# GPRS_ModuleV3R.net
KiCad netlist of a schematic drawn in Altium Designer
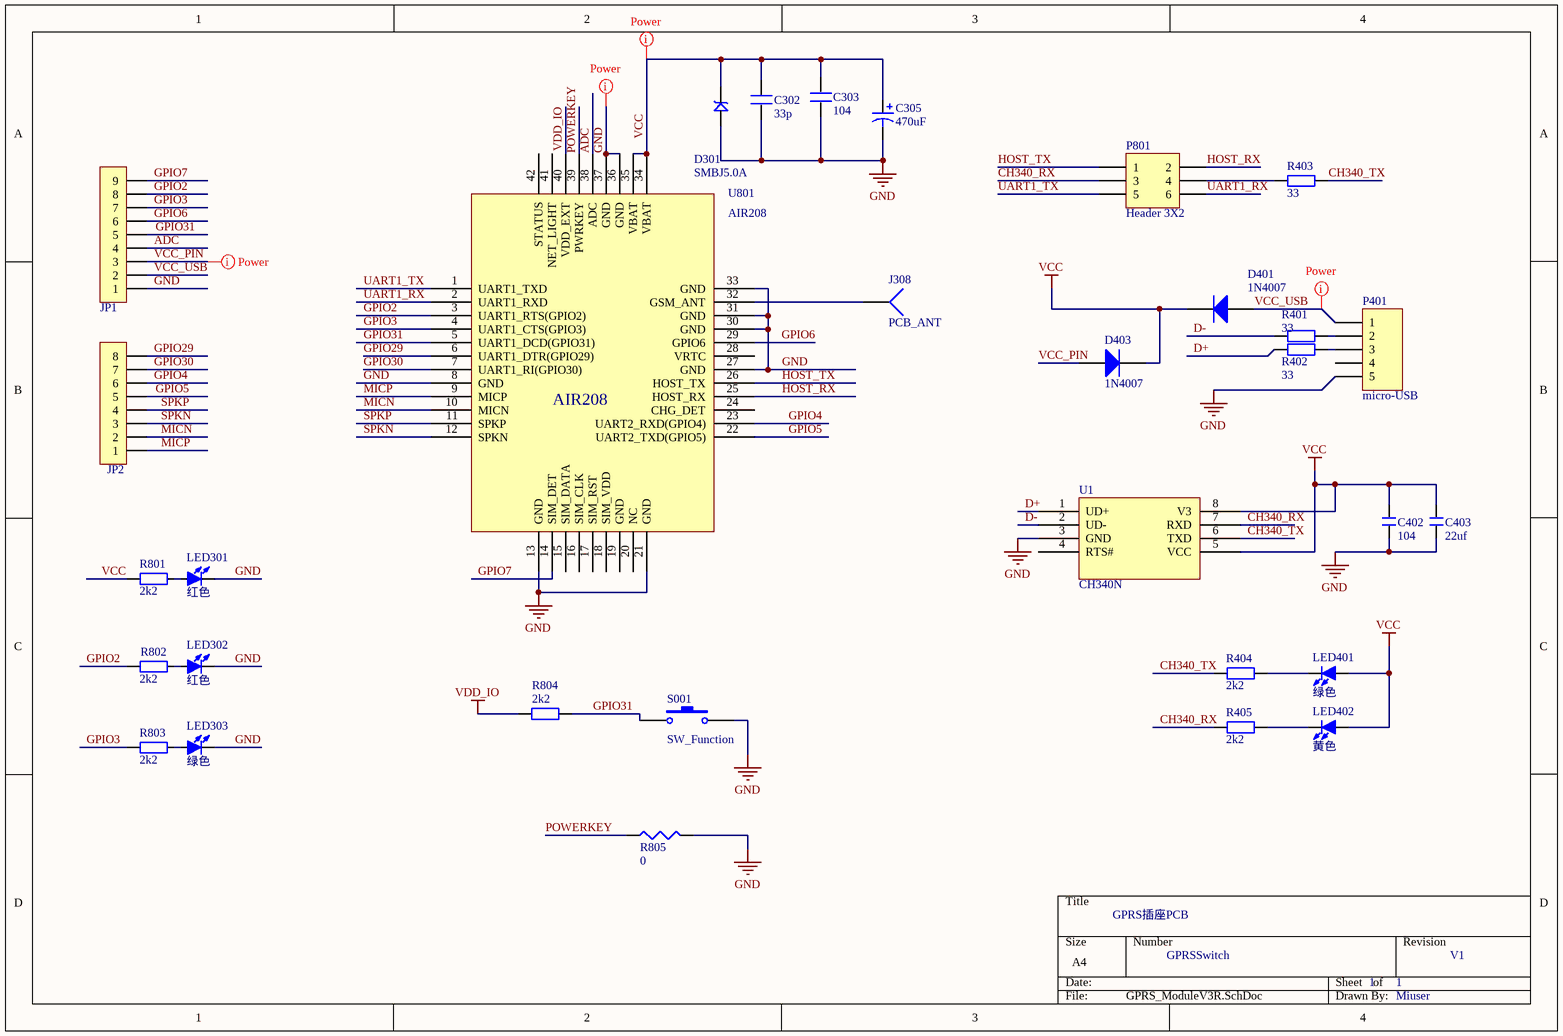
[diagram p0: GPRS_ModuleV3R.SchDoc]

(export (version "E")
  (design (tool "Eeschema 10.0.6"))
  (components
    (comp (ref "C302") (value "33p") (footprint "C 0603") (libsource (lib "PCB_Project") (part "C")))
    (comp (ref "C303") (value "104") (footprint "C 0805") (libsource (lib "PCB_Project") (part "C")))
    (comp (ref "C305")
      (value "470uF")
      (footprint "CD D(7343)")
      (description "Polarized Capacitor (Radial)")
      (fields (field (name "PUBLISHER") "Altium Limited"))
      (libsource (lib "Miscellaneous Devices") (part "Cap Pol1"))
    )
    (comp (ref "C402")
      (value "104")
      (footprint "C 0805")
      (description "无极性贴片电容")
      (fields (field (name "版权归属") "源创客"))
      (libsource (lib "电阻-电容-电感") (part "C"))
    )
    (comp (ref "C403")
      (value "22uf")
      (footprint "C 0805")
      (description "无极性贴片电容")
      (fields (field (name "版权归属") "源创客"))
      (libsource (lib "电阻-电容-电感") (part "C"))
    )
    (comp (ref "D301")
      (value "SMBJ5.0A")
      (footprint "SMC")
      (description "TVS")
      (fields (field (name "ALTIUM_UNNAMED_1") "SMBJ5.0A"))
      (libsource (lib "SIM800C 原理图库") (part "SMBJ"))
    )
    (comp (ref "D401")
      (value "1N4007")
      (footprint "SMB")
      (description "1 Amp General Purpose Rectifier")
      (fields (field (name "PUBLISHER") "Altium Limited"))
      (libsource (lib "Miscellaneous Devices") (part "Diode 1N4001"))
    )
    (comp (ref "D403")
      (value "1N4007")
      (footprint "SMB")
      (description "1 Amp General Purpose Rectifier")
      (fields (field (name "PUBLISHER") "Altium Limited"))
      (libsource (lib "Miscellaneous Devices") (part "Diode 1N4001"))
    )
    (comp (ref "J308")
      (value "PCB_ANT")
      (footprint "GSMANT2")
      (description "Socket")
      (fields (field (name "PUBLISHER") "Altium Limited"))
      (libsource (lib "PCB_Project") (part "Socket"))
    )
    (comp (ref "JP1")
      (value "HDR-1X9")
      (footprint "HDR-1X9")
      (description "9P接插件")
      (fields (field (name "版权归属") "源创客"))
      (libsource (lib "接插件") (part "Header 9"))
    )
    (comp (ref "JP2")
      (value "HDR-1X8")
      (footprint "HDR-1X8")
      (description "8P接插件")
      (fields (field (name "版权归属") "源创客"))
      (libsource (lib "接插件") (part "Header 8"))
    )
    (comp (ref "LED301")
      (value "红色")
      (footprint "LED 0603R")
      (description "贴片LED")
      (fields (field (name "版权归属") "源创客"))
      (libsource (lib "LED") (part "LED-SMD"))
    )
    (comp (ref "LED302")
      (value "红色")
      (footprint "LED 0603R")
      (description "贴片LED")
      (fields (field (name "版权归属") "源创客"))
      (libsource (lib "LED") (part "LED-SMD"))
    )
    (comp (ref "LED303")
      (value "绿色")
      (footprint "LED 0603G")
      (description "贴片LED")
      (fields (field (name "版权归属") "源创客"))
      (libsource (lib "LED") (part "LED-SMD"))
    )
    (comp (ref "LED401")
      (value "绿色")
      (footprint "LED 0603G")
      (description "贴片LED")
      (fields (field (name "版权归属") "源创客"))
      (libsource (lib "LED") (part "LED-SMD"))
    )
    (comp (ref "LED402")
      (value "黄色")
      (footprint "LED 0603Y")
      (description "贴片LED")
      (fields (field (name "版权归属") "源创客"))
      (libsource (lib "LED") (part "LED-SMD"))
    )
    (comp (ref "P401")
      (value "micro-USB")
      (footprint "通讯接口:USB-micro_B")
      (description "Header, 5-Pin")
      (fields (field (name "PUBLISHER") "Altium Limited"))
      (libsource (lib "Miscellaneous Connectors") (part "Header 5"))
    )
    (comp (ref "P801")
      (value "Header 3X2")
      (footprint "HDR2X3")
      (description "Header, 3-Pin, Dual row")
      (fields (field (name "PUBLISHER") "Altium Limited"))
      (libsource (lib "Miscellaneous Connectors") (part "Header 3X2"))
    )
    (comp (ref "R401")
      (value "33")
      (footprint "R 0603")
      (description "Resistor")
      (fields (field (name "PUBLISHER") "Altium Limited"))
      (libsource (lib "Miscellaneous Devices") (part "Res2"))
    )
    (comp (ref "R402")
      (value "33")
      (footprint "R 0603")
      (description "Resistor")
      (fields (field (name "PUBLISHER") "Altium Limited"))
      (libsource (lib "Miscellaneous Devices") (part "Res2"))
    )
    (comp (ref "R403")
      (value "33")
      (footprint "R 0603")
      (description "贴片电阻")
      (fields (field (name "版权归属") "源创客"))
      (libsource (lib "电阻-电容-电感") (part "R"))
    )
    (comp (ref "R404")
      (value "2k2")
      (footprint "R 0603")
      (description "贴片电阻")
      (fields (field (name "版权归属") "源创客"))
      (libsource (lib "电阻-电容-电感") (part "R"))
    )
    (comp (ref "R405")
      (value "2k2")
      (footprint "R 0603")
      (description "贴片电阻")
      (fields (field (name "版权归属") "源创客"))
      (libsource (lib "电阻-电容-电感") (part "R"))
    )
    (comp (ref "R801")
      (value "2k2")
      (footprint "R 0603")
      (description "贴片电阻")
      (fields (field (name "版权归属") "源创客"))
      (libsource (lib "电阻-电容-电感") (part "R"))
    )
    (comp (ref "R802")
      (value "2k2")
      (footprint "R 0603")
      (description "贴片电阻")
      (fields (field (name "版权归属") "源创客"))
      (libsource (lib "电阻-电容-电感") (part "R"))
    )
    (comp (ref "R803")
      (value "2k2")
      (footprint "R 0603")
      (description "贴片电阻")
      (fields (field (name "版权归属") "源创客"))
      (libsource (lib "电阻-电容-电感") (part "R"))
    )
    (comp (ref "R804")
      (value "2k2")
      (footprint "R 0603")
      (description "Resistor")
      (fields (field (name "PUBLISHER") "Altium Limited"))
      (libsource (lib "Miscellaneous Devices") (part "Res2"))
    )
    (comp (ref "R805")
      (value "0")
      (footprint "R 0603")
      (description "Resistor")
      (fields (field (name "PUBLISHER") "Altium Limited"))
      (libsource (lib "Miscellaneous Devices") (part "Res3"))
    )
    (comp (ref "S001")
      (value "SW_Function")
      (footprint "TSW SMD-3*6*2.5")
      (description "轻触开关/3x6x2.5")
      (fields (field (name "PUBLISHER") "Altium Limited"))
      (libsource (lib "Miscellaneous Devices") (part "SW-PB"))
    )
    (comp (ref "U1") (value "CH340N") (footprint "SOP8_M") (libsource (lib "mad") (part "CH340N")))
    (comp (ref "U801") (value "AIR208") (footprint "AIR208") (libsource (lib "mad") (part "AIR208")))
  )
  (nets
    (net (code "1") (name "/ADC") (class "Default")
      (node (ref "JP1") (pin "4") (pinfunction "4_4") (pintype "passive"))
      (node (ref "U801") (pin "38") (pinfunction "ADC_38") (pintype "passive"))
    )
    (net (code "2") (name "/CH340_RX") (class "Default")
      (node (ref "P801") (pin "3") (pinfunction "3_3") (pintype "passive"))
      (node (ref "R405") (pin "1") (pinfunction "1_1") (pintype "passive"))
      (node (ref "U1") (pin "7") (pinfunction "RXD_7") (pintype "passive"))
    )
    (net (code "3") (name "/CH340_TX") (class "Default")
      (node (ref "R403") (pin "2") (pinfunction "2_2") (pintype "passive"))
      (node (ref "R404") (pin "1") (pinfunction "1_1") (pintype "passive"))
      (node (ref "U1") (pin "6") (pinfunction "TXD_6") (pintype "passive"))
    )
    (net (code "4") (name "/D+") (class "Default")
      (node (ref "R402") (pin "1") (pinfunction "1_1") (pintype "passive"))
      (node (ref "U1") (pin "1") (pinfunction "UD+_1") (pintype "passive"))
    )
    (net (code "5") (name "/D-") (class "Default")
      (node (ref "R401") (pin "1") (pinfunction "1_1") (pintype "passive"))
      (node (ref "U1") (pin "2") (pinfunction "UD-_2") (pintype "passive"))
    )
    (net (code "6") (name "/GPIO2") (class "Default")
      (node (ref "JP1") (pin "8") (pinfunction "8_8") (pintype "passive"))
      (node (ref "R802") (pin "1") (pinfunction "1_1") (pintype "passive"))
      (node (ref "U801") (pin "3") (pinfunction "UART1_RTS(GPIO2)_3") (pintype "passive"))
    )
    (net (code "7") (name "/GPIO3") (class "Default")
      (node (ref "JP1") (pin "7") (pinfunction "7_7") (pintype "passive"))
      (node (ref "R803") (pin "1") (pinfunction "1_1") (pintype "passive"))
      (node (ref "U801") (pin "4") (pinfunction "UART1_CTS(GPIO3)_4") (pintype "passive"))
    )
    (net (code "8") (name "/GPIO4") (class "Default")
      (node (ref "JP2") (pin "6") (pinfunction "6_6") (pintype "passive"))
      (node (ref "U801") (pin "23") (pinfunction "UART2_RXD(GPIO4)_23") (pintype "passive"))
    )
    (net (code "9") (name "/GPIO5") (class "Default")
      (node (ref "JP2") (pin "5") (pinfunction "5_5") (pintype "passive"))
      (node (ref "U801") (pin "22") (pinfunction "UART2_TXD(GPIO5)_22") (pintype "passive"))
    )
    (net (code "10") (name "/GPIO6") (class "Default")
      (node (ref "JP1") (pin "6") (pinfunction "6_6") (pintype "passive"))
      (node (ref "U801") (pin "29") (pinfunction "GPIO6_29") (pintype "passive"))
    )
    (net (code "11") (name "/GPIO7") (class "Default")
      (node (ref "JP1") (pin "9") (pinfunction "9_9") (pintype "passive"))
      (node (ref "U801") (pin "14") (pinfunction "SIM_DET_14") (pintype "passive"))
    )
    (net (code "12") (name "/GPIO29") (class "Default")
      (node (ref "JP2") (pin "8") (pinfunction "8_8") (pintype "passive"))
      (node (ref "U801") (pin "6") (pinfunction "UART1_DTR(GPIO29)_6") (pintype "passive"))
    )
    (net (code "13") (name "/GPIO30") (class "Default")
      (node (ref "JP2") (pin "7") (pinfunction "7_7") (pintype "passive"))
      (node (ref "U801") (pin "7") (pinfunction "UART1_RI(GPIO30)_7") (pintype "passive"))
    )
    (net (code "14") (name "/GPIO31") (class "Default")
      (node (ref "JP1") (pin "5") (pinfunction "5_5") (pintype "passive"))
      (node (ref "R804") (pin "2") (pinfunction "2_2") (pintype "passive"))
      (node (ref "S001") (pin "1") (pinfunction "1_1") (pintype "passive"))
      (node (ref "U801") (pin "5") (pinfunction "UART1_DCD(GPIO31)_5") (pintype "passive"))
    )
    (net (code "15") (name "/HOST_RX") (class "Default")
      (node (ref "P801") (pin "2") (pinfunction "2_2") (pintype "passive"))
      (node (ref "U801") (pin "25") (pinfunction "HOST_RX_25") (pintype "passive"))
    )
    (net (code "16") (name "/HOST_TX") (class "Default")
      (node (ref "P801") (pin "1") (pinfunction "1_1") (pintype "passive"))
      (node (ref "U801") (pin "26") (pinfunction "HOST_TX_26") (pintype "passive"))
    )
    (net (code "17") (name "/MICN") (class "Default")
      (node (ref "JP2") (pin "2") (pinfunction "2_2") (pintype "passive"))
      (node (ref "U801") (pin "10") (pinfunction "MICN_10") (pintype "passive"))
    )
    (net (code "18") (name "/MICP") (class "Default")
      (node (ref "JP2") (pin "1") (pinfunction "1_1") (pintype "passive"))
      (node (ref "U801") (pin "9") (pinfunction "MICP_9") (pintype "passive"))
    )
    (net (code "19") (name "/POWERKEY") (class "Default")
      (node (ref "R805") (pin "1") (pinfunction "1_1") (pintype "passive"))
      (node (ref "U801") (pin "39") (pinfunction "PWRKEY_39") (pintype "passive"))
    )
    (net (code "20") (name "/SPKN") (class "Default")
      (node (ref "JP2") (pin "3") (pinfunction "3_3") (pintype "passive"))
      (node (ref "U801") (pin "12") (pinfunction "SPKN_12") (pintype "passive"))
    )
    (net (code "21") (name "/SPKP") (class "Default")
      (node (ref "JP2") (pin "4") (pinfunction "4_4") (pintype "passive"))
      (node (ref "U801") (pin "11") (pinfunction "SPKP_11") (pintype "passive"))
    )
    (net (code "22") (name "/UART1_RX") (class "Default")
      (node (ref "P801") (pin "6") (pinfunction "6_6") (pintype "passive"))
      (node (ref "U801") (pin "2") (pinfunction "UART1_RXD_2") (pintype "passive"))
    )
    (net (code "23") (name "/UART1_TX") (class "Default")
      (node (ref "P801") (pin "5") (pinfunction "5_5") (pintype "passive"))
      (node (ref "U801") (pin "1") (pinfunction "UART1_TXD_1") (pintype "passive"))
    )
    (net (code "24") (name "/VCC_PIN") (class "Default")
      (node (ref "D403") (pin "1") (pinfunction "A_1") (pintype "passive"))
      (node (ref "JP1") (pin "3") (pinfunction "3_3") (pintype "passive"))
    )
    (net (code "25") (name "/VCC_USB") (class "Default")
      (node (ref "D401") (pin "1") (pinfunction "A_1") (pintype "passive"))
      (node (ref "JP1") (pin "2") (pinfunction "2_2") (pintype "passive"))
      (node (ref "P401") (pin "1") (pinfunction "1_1") (pintype "passive"))
    )
    (net (code "26") (name "GND") (class "Default")
      (node (ref "C302") (pin "1") (pintype "passive"))
      (node (ref "C303") (pin "1") (pintype "passive"))
      (node (ref "C305") (pin "2") (pinfunction "2_2") (pintype "passive"))
      (node (ref "C402") (pin "1") (pinfunction "1_1") (pintype "passive"))
      (node (ref "C403") (pin "1") (pinfunction "1_1") (pintype "passive"))
      (node (ref "D301") (pin "1") (pintype "passive"))
      (node (ref "JP1") (pin "1") (pinfunction "1_1") (pintype "passive"))
      (node (ref "LED301") (pin "2") (pinfunction "K_2") (pintype "passive"))
      (node (ref "LED302") (pin "2") (pinfunction "K_2") (pintype "passive"))
      (node (ref "LED303") (pin "2") (pinfunction "K_2") (pintype "passive"))
      (node (ref "P401") (pin "5") (pinfunction "5_5") (pintype "passive"))
      (node (ref "R805") (pin "2") (pinfunction "2_2") (pintype "passive"))
      (node (ref "S001") (pin "2") (pinfunction "2_2") (pintype "passive"))
      (node (ref "U1") (pin "3") (pinfunction "GND_3") (pintype "passive"))
      (node (ref "U801") (pin "13") (pinfunction "GND_13") (pintype "passive"))
      (node (ref "U801") (pin "21") (pinfunction "GND_21") (pintype "passive"))
      (node (ref "U801") (pin "27") (pinfunction "GND_27") (pintype "passive"))
      (node (ref "U801") (pin "30") (pinfunction "GND_30") (pintype "passive"))
      (node (ref "U801") (pin "31") (pinfunction "GND_31") (pintype "passive"))
      (node (ref "U801") (pin "33") (pinfunction "GND_33") (pintype "passive"))
      (node (ref "U801") (pin "36") (pinfunction "GND_36") (pintype "passive"))
      (node (ref "U801") (pin "37") (pinfunction "GND_37") (pintype "passive"))
      (node (ref "U801") (pin "8") (pinfunction "GND_8") (pintype "passive"))
    )
    (net (code "27") (name "Net-(LED301-A)") (class "Default")
      (node (ref "LED301") (pin "1") (pinfunction "A_1") (pintype "passive"))
      (node (ref "R801") (pin "2") (pinfunction "2_2") (pintype "passive"))
    )
    (net (code "28") (name "Net-(LED302-A)") (class "Default")
      (node (ref "LED302") (pin "1") (pinfunction "A_1") (pintype "passive"))
      (node (ref "R802") (pin "2") (pinfunction "2_2") (pintype "passive"))
    )
    (net (code "29") (name "Net-(LED303-A)") (class "Default")
      (node (ref "LED303") (pin "1") (pinfunction "A_1") (pintype "passive"))
      (node (ref "R803") (pin "2") (pinfunction "2_2") (pintype "passive"))
    )
    (net (code "30") (name "Net-(LED401-K)") (class "Default")
      (node (ref "LED401") (pin "2") (pinfunction "K_2") (pintype "passive"))
      (node (ref "R404") (pin "2") (pinfunction "2_2") (pintype "passive"))
    )
    (net (code "31") (name "Net-(LED402-K)") (class "Default")
      (node (ref "LED402") (pin "2") (pinfunction "K_2") (pintype "passive"))
      (node (ref "R405") (pin "2") (pinfunction "2_2") (pintype "passive"))
    )
    (net (code "32") (name "Net-(P401-Pad2)") (class "Default")
      (node (ref "P401") (pin "2") (pinfunction "2_2") (pintype "passive"))
      (node (ref "R401") (pin "2") (pinfunction "2_2") (pintype "passive"))
    )
    (net (code "33") (name "Net-(P401-Pad3)") (class "Default")
      (node (ref "P401") (pin "3") (pinfunction "3_3") (pintype "passive"))
      (node (ref "R402") (pin "2") (pinfunction "2_2") (pintype "passive"))
    )
    (net (code "34") (name "Net-(P801-Pad4)") (class "Default")
      (node (ref "P801") (pin "4") (pinfunction "4_4") (pintype "passive"))
      (node (ref "R403") (pin "1") (pinfunction "1_1") (pintype "passive"))
    )
    (net (code "35") (name "Net-(U801-GSM_ANT)") (class "Default")
      (node (ref "J308") (pin "1") (pinfunction "1_1") (pintype "passive"))
      (node (ref "U801") (pin "32") (pinfunction "GSM_ANT_32") (pintype "passive"))
    )
    (net (code "36") (name "VCC") (class "Default")
      (node (ref "C302") (pin "2") (pintype "passive"))
      (node (ref "C303") (pin "2") (pintype "passive"))
      (node (ref "C305") (pin "1") (pinfunction "1_1") (pintype "passive"))
      (node (ref "C402") (pin "2") (pinfunction "2_2") (pintype "passive"))
      (node (ref "C403") (pin "2") (pinfunction "2_2") (pintype "passive"))
      (node (ref "D301") (pin "2") (pintype "passive"))
      (node (ref "D401") (pin "2") (pinfunction "K_2") (pintype "passive"))
      (node (ref "D403") (pin "2") (pinfunction "K_2") (pintype "passive"))
      (node (ref "LED401") (pin "1") (pinfunction "A_1") (pintype "passive"))
      (node (ref "LED402") (pin "1") (pinfunction "A_1") (pintype "passive"))
      (node (ref "R801") (pin "1") (pinfunction "1_1") (pintype "passive"))
      (node (ref "U1") (pin "5") (pinfunction "VCC_5") (pintype "passive"))
      (node (ref "U1") (pin "8") (pinfunction "V3_8") (pintype "passive"))
      (node (ref "U801") (pin "34") (pinfunction "VBAT_34") (pintype "passive"))
      (node (ref "U801") (pin "35") (pinfunction "VBAT_35") (pintype "passive"))
    )
    (net (code "37") (name "VDD_IO") (class "Default")
      (node (ref "R804") (pin "1") (pinfunction "1_1") (pintype "passive"))
      (node (ref "U801") (pin "40") (pinfunction "VDD_EXT_40") (pintype "passive"))
    )
    (net (code "38") (name "unconnected-(P401-Pad4)") (class "Default")
      (node (ref "P401") (pin "4") (pinfunction "4_4") (pintype "passive"))
    )
    (net (code "39") (name "unconnected-(U1-RTS#-Pad4)") (class "Default")
      (node (ref "U1") (pin "4") (pinfunction "RTS#_4") (pintype "passive"))
    )
    (net (code "40") (name "unconnected-(U801-CHG_DET-Pad24)") (class "Default")
      (node (ref "U801") (pin "24") (pinfunction "CHG_DET_24") (pintype "passive"))
    )
    (net (code "41") (name "unconnected-(U801-GND-Pad19)") (class "Default")
      (node (ref "U801") (pin "19") (pinfunction "GND_19") (pintype "passive"))
    )
    (net (code "42") (name "unconnected-(U801-NC-Pad20)") (class "Default")
      (node (ref "U801") (pin "20") (pinfunction "NC_20") (pintype "passive"))
    )
    (net (code "43") (name "unconnected-(U801-NET_LIGHT-Pad41)") (class "Default")
      (node (ref "U801") (pin "41") (pinfunction "NET_LIGHT_41") (pintype "passive"))
    )
    (net (code "44") (name "unconnected-(U801-SIM_CLK-Pad16)") (class "Default")
      (node (ref "U801") (pin "16") (pinfunction "SIM_CLK_16") (pintype "passive"))
    )
    (net (code "45") (name "unconnected-(U801-SIM_DATA-Pad15)") (class "Default")
      (node (ref "U801") (pin "15") (pinfunction "SIM_DATA_15") (pintype "passive"))
    )
    (net (code "46") (name "unconnected-(U801-SIM_RST-Pad17)") (class "Default")
      (node (ref "U801") (pin "17") (pinfunction "SIM_RST_17") (pintype "passive"))
    )
    (net (code "47") (name "unconnected-(U801-SIM_VDD-Pad18)") (class "Default")
      (node (ref "U801") (pin "18") (pinfunction "SIM_VDD_18") (pintype "passive"))
    )
    (net (code "48") (name "unconnected-(U801-STATUS-Pad42)") (class "Default")
      (node (ref "U801") (pin "42") (pinfunction "STATUS_42") (pintype "passive"))
    )
    (net (code "49") (name "unconnected-(U801-VRTC-Pad28)") (class "Default")
      (node (ref "U801") (pin "28") (pinfunction "VRTC_28") (pintype "passive"))
    )
  )
)
